# Imaging_Sensor.net
KiCad netlist of a schematic drawn in Altium Designer
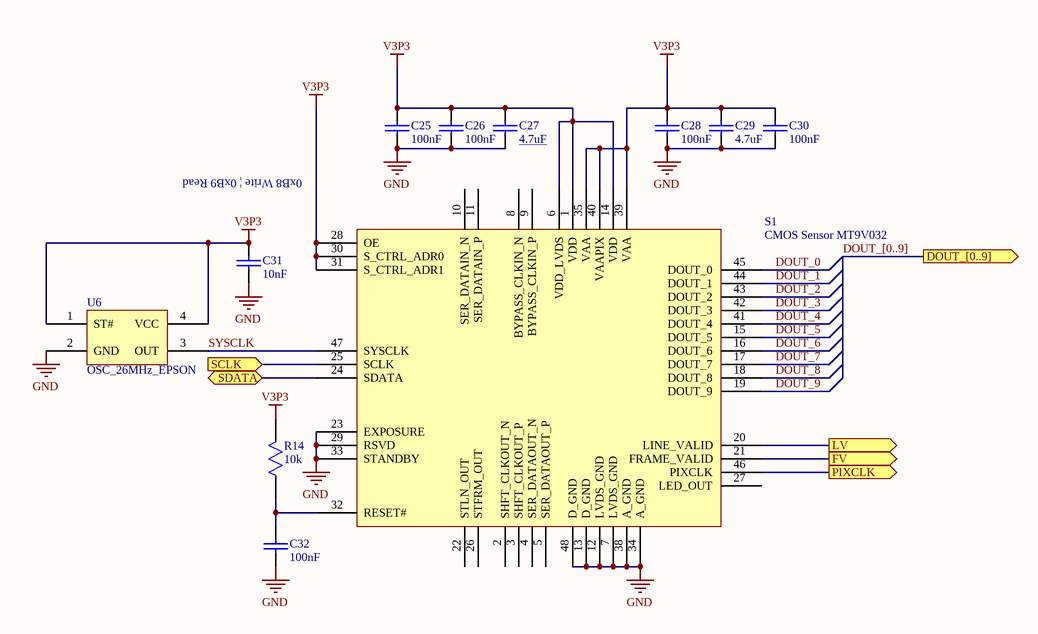
[diagram p0: Imaging_Sensor.SchDoc]

(export (version "E")
  (design (tool "Eeschema 10.0.6"))
  (components
    (comp (ref "C25")
      (value "100nF")
      (footprint "SMD CAP 0402")
      (libsource (lib "DA_Component_Library") (part "Capacitor"))
    )
    (comp (ref "C26")
      (value "100nF")
      (footprint "SMD CAP 0402")
      (libsource (lib "DA_Component_Library") (part "Capacitor"))
    )
    (comp (ref "C27")
      (value "4.7uF")
      (footprint "SMD CAP 0402")
      (libsource (lib "DA_Component_Library") (part "Capacitor"))
    )
    (comp (ref "C28")
      (value "100nF")
      (footprint "SMD CAP 0402")
      (libsource (lib "DA_Component_Library") (part "Capacitor"))
    )
    (comp (ref "C29")
      (value "4.7uF")
      (footprint "SMD CAP 0402")
      (libsource (lib "DA_Component_Library") (part "Capacitor"))
    )
    (comp (ref "C30")
      (value "100nF")
      (footprint "SMD CAP 0402")
      (libsource (lib "DA_Component_Library") (part "Capacitor"))
    )
    (comp (ref "C31")
      (value "10nF")
      (footprint "SMD CAP 0402")
      (libsource (lib "DA_Component_Library") (part "Capacitor"))
    )
    (comp (ref "C32")
      (value "100nF")
      (footprint "SMD CAP 0402")
      (libsource (lib "DA_Component_Library") (part "Capacitor"))
    )
    (comp (ref "R14")
      (value "10k")
      (footprint "SMD RES 0402")
      (libsource (lib "DA_Component_Library") (part "Resistor"))
    )
    (comp (ref "S1")
      (value "CMOS Sensor MT9V032")
      (footprint "CMOS Sensor MT9V032_HD")
      (libsource (lib "DA_Component_Library") (part "CMOS Sensor MT9V032"))
    )
    (comp (ref "U6")
      (value "OSC_26MHz_EPSON")
      (footprint "OSC SG_211SCE 26MHz")
      (libsource (lib "DA_Component_Library") (part "OSC_26MHz_EPSON"))
    )
  )
  (nets
    (net (code "1") (name "/DOUT_0") (class "Default")
      (node (ref "S1") (pin "45") (pinfunction "DOUT_0_45") (pintype "passive"))
    )
    (net (code "2") (name "/DOUT_1") (class "Default")
      (node (ref "S1") (pin "44") (pinfunction "DOUT_1_44") (pintype "passive"))
    )
    (net (code "3") (name "/DOUT_2") (class "Default")
      (node (ref "S1") (pin "43") (pinfunction "DOUT_2_43") (pintype "passive"))
    )
    (net (code "4") (name "/DOUT_3") (class "Default")
      (node (ref "S1") (pin "42") (pinfunction "DOUT_3_42") (pintype "passive"))
    )
    (net (code "5") (name "/DOUT_4") (class "Default")
      (node (ref "S1") (pin "41") (pinfunction "DOUT_4_41") (pintype "passive"))
    )
    (net (code "6") (name "/DOUT_5") (class "Default")
      (node (ref "S1") (pin "15") (pinfunction "DOUT_5_15") (pintype "passive"))
    )
    (net (code "7") (name "/DOUT_6") (class "Default")
      (node (ref "S1") (pin "16") (pinfunction "DOUT_6_16") (pintype "passive"))
    )
    (net (code "8") (name "/DOUT_7") (class "Default")
      (node (ref "S1") (pin "17") (pinfunction "DOUT_7_17") (pintype "passive"))
    )
    (net (code "9") (name "/DOUT_8") (class "Default")
      (node (ref "S1") (pin "18") (pinfunction "DOUT_8_18") (pintype "passive"))
    )
    (net (code "10") (name "/DOUT_9") (class "Default")
      (node (ref "S1") (pin "19") (pinfunction "DOUT_9_19") (pintype "passive"))
    )
    (net (code "12") (name "/FV") (class "Default")
      (node (ref "S1") (pin "21") (pinfunction "FRAME_VALID_21") (pintype "passive"))
    )
    (net (code "13") (name "/LV") (class "Default")
      (node (ref "S1") (pin "20") (pinfunction "LINE_VALID_20") (pintype "passive"))
    )
    (net (code "14") (name "/PIXCLK") (class "Default")
      (node (ref "S1") (pin "46") (pinfunction "PIXCLK_46") (pintype "passive"))
    )
    (net (code "15") (name "/SCLK") (class "Default")
      (node (ref "S1") (pin "25") (pinfunction "SCLK_25") (pintype "passive"))
    )
    (net (code "16") (name "/SDATA") (class "Default")
      (node (ref "S1") (pin "24") (pinfunction "SDATA_24") (pintype "passive"))
    )
    (net (code "17") (name "/SYSCLK") (class "Default")
      (node (ref "S1") (pin "47") (pinfunction "SYSCLK_47") (pintype "passive"))
      (node (ref "U6") (pin "3") (pinfunction "OUT_3") (pintype "passive"))
    )
    (net (code "18") (name "GND") (class "Default")
      (node (ref "C25") (pin "1") (pinfunction "1_1") (pintype "passive"))
      (node (ref "C26") (pin "1") (pinfunction "1_1") (pintype "passive"))
      (node (ref "C27") (pin "1") (pinfunction "1_1") (pintype "passive"))
      (node (ref "C28") (pin "1") (pinfunction "1_1") (pintype "passive"))
      (node (ref "C29") (pin "1") (pinfunction "1_1") (pintype "passive"))
      (node (ref "C30") (pin "1") (pinfunction "1_1") (pintype "passive"))
      (node (ref "C31") (pin "1") (pinfunction "1_1") (pintype "passive"))
      (node (ref "C32") (pin "1") (pinfunction "1_1") (pintype "passive"))
      (node (ref "S1") (pin "12") (pinfunction "LVDS_GND_12") (pintype "passive"))
      (node (ref "S1") (pin "13") (pinfunction "D_GND_13") (pintype "passive"))
      (node (ref "S1") (pin "23") (pinfunction "EXPOSURE_23") (pintype "passive"))
      (node (ref "S1") (pin "29") (pinfunction "RSVD_29") (pintype "passive"))
      (node (ref "S1") (pin "33") (pinfunction "STANDBY_33") (pintype "passive"))
      (node (ref "S1") (pin "34") (pinfunction "A_GND_34") (pintype "passive"))
      (node (ref "S1") (pin "38") (pinfunction "A_GND_38") (pintype "passive"))
      (node (ref "S1") (pin "48") (pinfunction "D_GND_48") (pintype "passive"))
      (node (ref "S1") (pin "7") (pinfunction "LVDS_GND_7") (pintype "passive"))
      (node (ref "U6") (pin "2") (pinfunction "GND_2") (pintype "passive"))
    )
    (net (code "19") (name "Net-(S1-RESET#)") (class "Default")
      (node (ref "C32") (pin "0") (pinfunction "0_0") (pintype "passive"))
      (node (ref "R14") (pin "0") (pinfunction "0_0") (pintype "passive"))
      (node (ref "S1") (pin "32") (pinfunction "RESET#_32") (pintype "passive"))
    )
    (net (code "20") (name "V3P3") (class "Default")
      (node (ref "C25") (pin "0") (pinfunction "0_0") (pintype "passive"))
      (node (ref "C26") (pin "0") (pinfunction "0_0") (pintype "passive"))
      (node (ref "C27") (pin "0") (pinfunction "0_0") (pintype "passive"))
      (node (ref "C28") (pin "0") (pinfunction "0_0") (pintype "passive"))
      (node (ref "C29") (pin "0") (pinfunction "0_0") (pintype "passive"))
      (node (ref "C30") (pin "0") (pinfunction "0_0") (pintype "passive"))
      (node (ref "C31") (pin "0") (pinfunction "0_0") (pintype "passive"))
      (node (ref "R14") (pin "1") (pinfunction "1_1") (pintype "passive"))
      (node (ref "S1") (pin "1") (pinfunction "VDD_1") (pintype "passive"))
      (node (ref "S1") (pin "14") (pinfunction "VDD_14") (pintype "passive"))
      (node (ref "S1") (pin "28") (pinfunction "OE_28") (pintype "passive"))
      (node (ref "S1") (pin "30") (pinfunction "S_CTRL_ADR0_30") (pintype "passive"))
      (node (ref "S1") (pin "31") (pinfunction "S_CTRL_ADR1_31") (pintype "passive"))
      (node (ref "S1") (pin "35") (pinfunction "VAA_35") (pintype "passive"))
      (node (ref "S1") (pin "39") (pinfunction "VAA_39") (pintype "passive"))
      (node (ref "S1") (pin "40") (pinfunction "VAAPIX_40") (pintype "passive"))
      (node (ref "S1") (pin "6") (pinfunction "VDD_LVDS_6") (pintype "passive"))
      (node (ref "U6") (pin "1") (pinfunction "ST#_1") (pintype "passive"))
      (node (ref "U6") (pin "4") (pinfunction "VCC_4") (pintype "passive"))
    )
    (net (code "21") (name "unconnected-(S1-BYPASS_CLKIN_N-Pad8)") (class "Default")
      (node (ref "S1") (pin "8") (pinfunction "BYPASS_CLKIN_N_8") (pintype "passive"))
    )
    (net (code "22") (name "unconnected-(S1-BYPASS_CLKIN_P-Pad9)") (class "Default")
      (node (ref "S1") (pin "9") (pinfunction "BYPASS_CLKIN_P_9") (pintype "passive"))
    )
    (net (code "23") (name "unconnected-(S1-LED_OUT-Pad27)") (class "Default")
      (node (ref "S1") (pin "27") (pinfunction "LED_OUT_27") (pintype "passive"))
    )
    (net (code "24") (name "unconnected-(S1-SER_DATAIN_N-Pad10)") (class "Default")
      (node (ref "S1") (pin "10") (pinfunction "SER_DATAIN_N_10") (pintype "passive"))
    )
    (net (code "25") (name "unconnected-(S1-SER_DATAIN_P-Pad11)") (class "Default")
      (node (ref "S1") (pin "11") (pinfunction "SER_DATAIN_P_11") (pintype "passive"))
    )
    (net (code "26") (name "unconnected-(S1-SER_DATAOUT_N-Pad4)") (class "Default")
      (node (ref "S1") (pin "4") (pinfunction "SER_DATAOUT_N_4") (pintype "passive"))
    )
    (net (code "27") (name "unconnected-(S1-SER_DATAOUT_P-Pad5)") (class "Default")
      (node (ref "S1") (pin "5") (pinfunction "SER_DATAOUT_P_5") (pintype "passive"))
    )
    (net (code "28") (name "unconnected-(S1-SHFT_CLKOUT_N-Pad2)") (class "Default")
      (node (ref "S1") (pin "2") (pinfunction "SHFT_CLKOUT_N_2") (pintype "passive"))
    )
    (net (code "29") (name "unconnected-(S1-SHFT_CLKOUT_P-Pad3)") (class "Default")
      (node (ref "S1") (pin "3") (pinfunction "SHFT_CLKOUT_P_3") (pintype "passive"))
    )
    (net (code "30") (name "unconnected-(S1-STFRM_OUT-Pad26)") (class "Default")
      (node (ref "S1") (pin "26") (pinfunction "STFRM_OUT_26") (pintype "passive"))
    )
    (net (code "31") (name "unconnected-(S1-STLN_OUT-Pad22)") (class "Default")
      (node (ref "S1") (pin "22") (pinfunction "STLN_OUT_22") (pintype "passive"))
    )
  )
)
